# ADC.net
KiCad netlist of a schematic drawn in Altium Designer
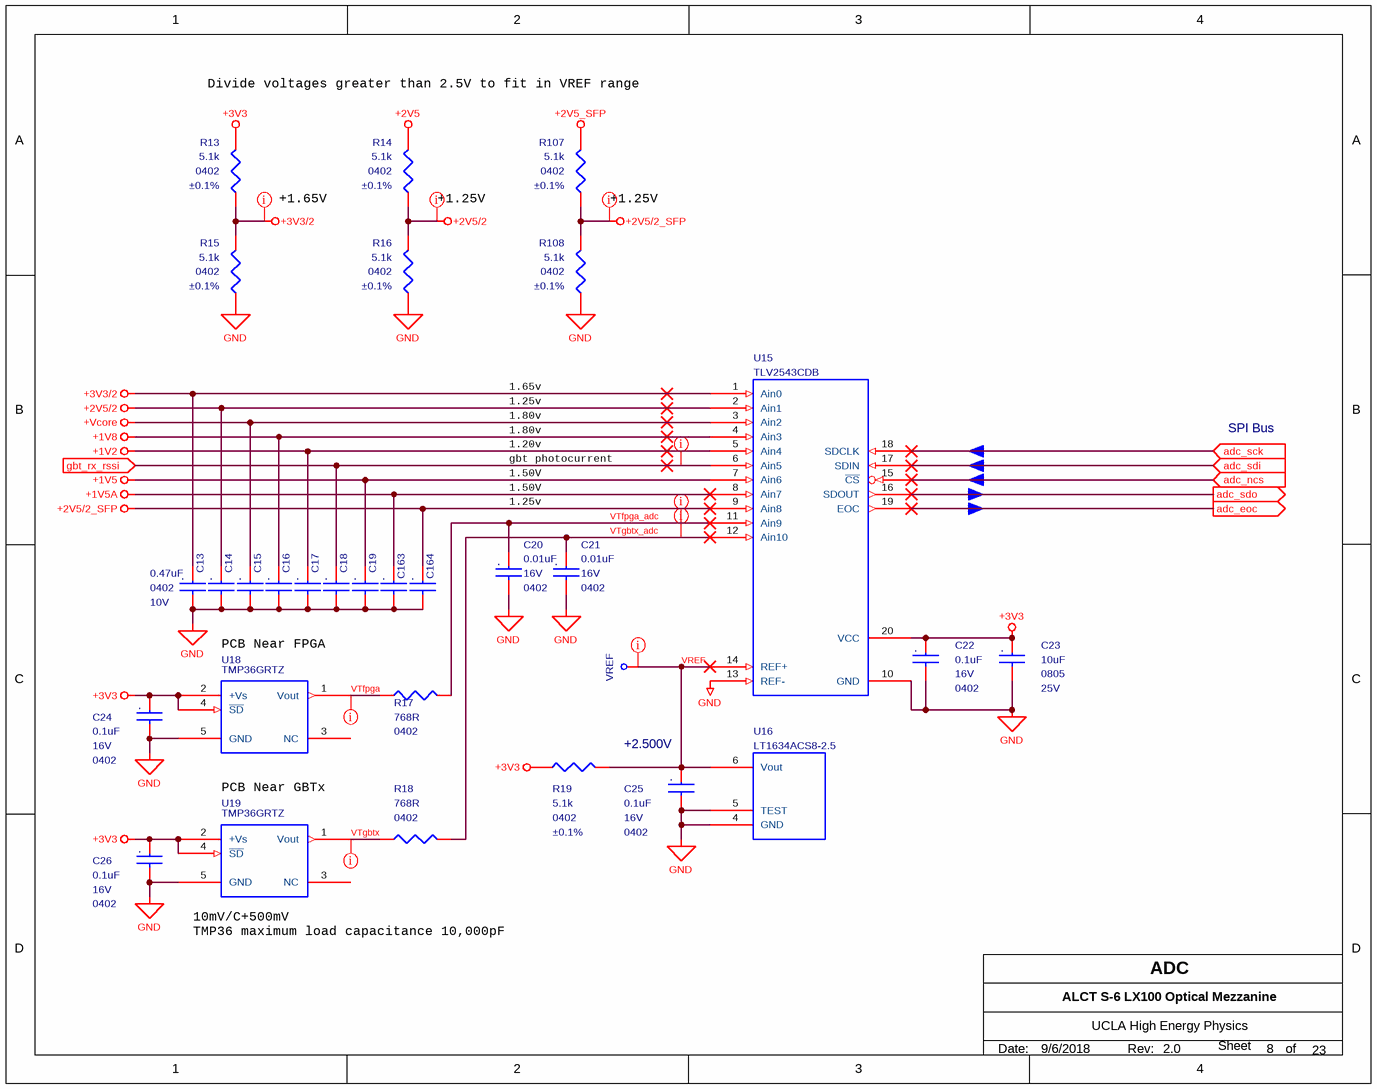
[diagram p0: ADC.SchDoc]

(export (version "E")
  (design (tool "Eeschema 10.0.6"))
  (components
    (comp (ref "C13")
      (value "0.47uF")
      (footprint "MC_S6/SM/C_0402_IPC")
      (description "CAP CER 0.47UF 10V X5R 0402")
      (fields
        (field (name "MANUFACTURER") "Murata Electronics North America")
        (field (name "MANUFACTURER PART NUMBER") "GRM155R61A474KE15D")
        (field (name "PACKAGE") "0402")
        (field (name "VOLTAGE - RATED") "10V")
      )
      (libsource (lib "ALCT_MEZ_SPARTAN6_Library") (part "GRM155R61A474KE15D"))
    )
    (comp (ref "C14")
      (value "0.47uF")
      (footprint "MC_S6/SM/C_0402_IPC")
      (description "CAP CER 0.47UF 10V X5R 0402")
      (fields
        (field (name "MANUFACTURER") "Murata Electronics North America")
        (field (name "MANUFACTURER PART NUMBER") "GRM155R61A474KE15D")
      )
      (libsource (lib "ALCT_MEZ_SPARTAN6_Library") (part "GRM155R61A474KE15D"))
    )
    (comp (ref "C15")
      (value "0.47uF")
      (footprint "MC_S6/SM/C_0402_IPC")
      (description "CAP CER 0.47UF 10V X5R 0402")
      (fields
        (field (name "MANUFACTURER") "Murata Electronics North America")
        (field (name "MANUFACTURER PART NUMBER") "GRM155R61A474KE15D")
      )
      (libsource (lib "ALCT_MEZ_SPARTAN6_Library") (part "GRM155R61A474KE15D"))
    )
    (comp (ref "C16")
      (value "0.47uF")
      (footprint "MC_S6/SM/C_0402_IPC")
      (description "CAP CER 0.47UF 10V X5R 0402")
      (fields
        (field (name "MANUFACTURER") "Murata Electronics North America")
        (field (name "MANUFACTURER PART NUMBER") "GRM155R61A474KE15D")
      )
      (libsource (lib "ALCT_MEZ_SPARTAN6_Library") (part "GRM155R61A474KE15D"))
    )
    (comp (ref "C17")
      (value "0.47uF")
      (footprint "MC_S6/SM/C_0402_IPC")
      (description "CAP CER 0.47UF 10V X5R 0402")
      (fields
        (field (name "MANUFACTURER") "Murata Electronics North America")
        (field (name "MANUFACTURER PART NUMBER") "GRM155R61A474KE15D")
      )
      (libsource (lib "ALCT_MEZ_SPARTAN6_Library") (part "GRM155R61A474KE15D"))
    )
    (comp (ref "C18")
      (value "0.47uF")
      (footprint "MC_S6/SM/C_0402_IPC")
      (description "CAP CER 0.47UF 10V X5R 0402")
      (fields
        (field (name "MANUFACTURER") "Murata Electronics North America")
        (field (name "MANUFACTURER PART NUMBER") "GRM155R61A474KE15D")
      )
      (libsource (lib "ALCT_MEZ_SPARTAN6_Library") (part "GRM155R61A474KE15D"))
    )
    (comp (ref "C19")
      (value "0.47uF")
      (footprint "MC_S6/SM/C_0402_IPC")
      (description "CAP CER 0.47UF 10V X5R 0402")
      (fields
        (field (name "MANUFACTURER") "Murata Electronics North America")
        (field (name "MANUFACTURER PART NUMBER") "GRM155R61A474KE15D")
      )
      (libsource (lib "ALCT_MEZ_SPARTAN6_Library") (part "GRM155R61A474KE15D"))
    )
    (comp (ref "C20")
      (value "0.01uF")
      (footprint "MC_S6/SM/C_0402_IPC")
      (description "CAP CER 10nF 16V X7R 0402")
      (fields
        (field (name "MANUFACTURER") "KEMET")
        (field (name "MANUFACTURER PART NUMBER") "C0402C103K4RACTU")
        (field (name "VOLTAGE - RATED") "16V")
        (field (name "PACKAGE") "0402")
      )
      (libsource (lib "ALCT_MEZ_SPARTAN6_Library") (part "C0402C103K4RACTU"))
    )
    (comp (ref "C21")
      (value "0.01uF")
      (footprint "MC_S6/SM/C_0402_IPC")
      (description "CAP CER 10nF 16V X7R 0402")
      (fields
        (field (name "MANUFACTURER") "KEMET")
        (field (name "MANUFACTURER PART NUMBER") "C0402C103K4RACTU")
        (field (name "VOLTAGE - RATED") "16V")
        (field (name "PACKAGE") "0402")
      )
      (libsource (lib "ALCT_MEZ_SPARTAN6_Library") (part "C0402C103K4RACTU"))
    )
    (comp (ref "C22")
      (value "0.1uF")
      (footprint "MC_S6/SM/C_0402_IPC")
      (description "CAP CER 0.1UF 16V X7R 0402")
      (fields
        (field (name "MANUFACTURER") "KEMET")
        (field (name "MANUFACTURER PART NUMBER") "C0402C104K4RACTU")
        (field (name "PACKAGE") "0402")
        (field (name "VOLTAGE - RATED") "16V")
      )
      (libsource (lib "ALCT_MEZ_SPARTAN6_Library") (part "C0402C104K4RACTU"))
    )
    (comp (ref "C23")
      (value "10uF")
      (footprint "MC_S6/SM/C_0805_IPC")
      (description "CAP CER 10UF 25V X5R 0805")
      (fields
        (field (name "MANUFACTURER") "Murata Electronics North America")
        (field (name "MANUFACTURER PART NUMBER") "GRM21BR61E106KA73L")
        (field (name "VOLTAGE - RATED") "25V")
        (field (name "PACKAGE") "0805")
      )
      (libsource (lib "ALCT_MEZ_SPARTAN6_Library") (part "GRM21BR61E106KA73L"))
    )
    (comp (ref "C24")
      (value "0.1uF")
      (footprint "MC_S6/SM/C_0402_IPC")
      (description "CAP CER 0.1UF 16V X7R 0402")
      (fields
        (field (name "MANUFACTURER") "KEMET")
        (field (name "MANUFACTURER PART NUMBER") "C0402C104K4RACTU")
        (field (name "PACKAGE") "0402")
        (field (name "VOLTAGE - RATED") "16V")
      )
      (libsource (lib "ALCT_MEZ_SPARTAN6_Library") (part "C0402C104K4RACTU"))
    )
    (comp (ref "C25")
      (value "0.1uF")
      (footprint "MC_S6/SM/C_0402_IPC")
      (description "CAP CER 0.1UF 16V X7R 0402")
      (fields
        (field (name "MANUFACTURER") "KEMET")
        (field (name "MANUFACTURER PART NUMBER") "C0402C104K4RACTU")
        (field (name "PACKAGE") "0402")
        (field (name "VOLTAGE - RATED") "16V")
      )
      (libsource (lib "ALCT_MEZ_SPARTAN6_Library") (part "C0402C104K4RACTU"))
    )
    (comp (ref "C26")
      (value "0.1uF")
      (footprint "MC_S6/SM/C_0402_IPC")
      (description "CAP CER 0.1UF 16V X7R 0402")
      (fields
        (field (name "MANUFACTURER") "KEMET")
        (field (name "MANUFACTURER PART NUMBER") "C0402C104K4RACTU")
        (field (name "PACKAGE") "0402")
        (field (name "VOLTAGE - RATED") "16V")
      )
      (libsource (lib "ALCT_MEZ_SPARTAN6_Library") (part "C0402C104K4RACTU"))
    )
    (comp (ref "C163")
      (value "0.47uF")
      (footprint "MC_S6/SM/C_0402_IPC")
      (description "CAP CER 0.47UF 10V X5R 0402")
      (fields
        (field (name "MANUFACTURER") "Murata Electronics North America")
        (field (name "MANUFACTURER PART NUMBER") "GRM155R61A474KE15D")
      )
      (libsource (lib "ALCT_MEZ_SPARTAN6_Library") (part "GRM155R61A474KE15D"))
    )
    (comp (ref "C164")
      (value "0.47uF")
      (footprint "MC_S6/SM/C_0402_IPC")
      (description "CAP CER 0.47UF 10V X5R 0402")
      (fields
        (field (name "MANUFACTURER") "Murata Electronics North America")
        (field (name "MANUFACTURER PART NUMBER") "GRM155R61A474KE15D")
      )
      (libsource (lib "ALCT_MEZ_SPARTAN6_Library") (part "GRM155R61A474KE15D"))
    )
    (comp (ref "R13")
      (value "5.1k")
      (footprint "MC_S6/SM/R_0402_IPC")
      (description "RES SMD 5.1K OHM 0.1% 1/16W 0402")
      (fields
        (field (name "TOLERANCE") "±0.1%")
        (field (name "MANUFACTURER") "Panasonic Electronic Components")
        (field (name "MANUFACTURER PART NUMBER") "ERA-2AEB512X")
        (field (name "SUPPLIER DEVICE PACKAGE") "0402")
      )
      (libsource (lib "ALCT_MEZ_SPARTAN6_Library") (part "ERA-2AEB512X"))
    )
    (comp (ref "R14")
      (value "5.1k")
      (footprint "MC_S6/SM/R_0402_IPC")
      (description "RES SMD 5.1K OHM 0.1% 1/16W 0402")
      (fields
        (field (name "TOLERANCE") "±0.1%")
        (field (name "MANUFACTURER") "Panasonic Electronic Components")
        (field (name "MANUFACTURER PART NUMBER") "ERA-2AEB512X")
        (field (name "SUPPLIER DEVICE PACKAGE") "0402")
      )
      (libsource (lib "ALCT_MEZ_SPARTAN6_Library") (part "ERA-2AEB512X"))
    )
    (comp (ref "R15")
      (value "5.1k")
      (footprint "MC_S6/SM/R_0402_IPC")
      (description "RES SMD 5.1K OHM 0.1% 1/16W 0402")
      (fields
        (field (name "TOLERANCE") "±0.1%")
        (field (name "MANUFACTURER") "Panasonic Electronic Components")
        (field (name "MANUFACTURER PART NUMBER") "ERA-2AEB512X")
        (field (name "SUPPLIER DEVICE PACKAGE") "0402")
      )
      (libsource (lib "ALCT_MEZ_SPARTAN6_Library") (part "ERA-2AEB512X"))
    )
    (comp (ref "R16")
      (value "5.1k")
      (footprint "MC_S6/SM/R_0402_IPC")
      (description "RES SMD 5.1K OHM 0.1% 1/16W 0402")
      (fields
        (field (name "TOLERANCE") "±0.1%")
        (field (name "MANUFACTURER") "Panasonic Electronic Components")
        (field (name "MANUFACTURER PART NUMBER") "ERA-2AEB512X")
        (field (name "SUPPLIER DEVICE PACKAGE") "0402")
      )
      (libsource (lib "ALCT_MEZ_SPARTAN6_Library") (part "ERA-2AEB512X"))
    )
    (comp (ref "R17")
      (value "768R")
      (footprint "MC_S6/SM/R_0402_IPC")
      (description "RES SMD 768 OHM 5.0% 1/10W 0402")
      (fields
        (field (name "TOLERANCE") "±1%")
        (field (name "MANUFACTURER") "Panasonic Electronic Components")
        (field (name "SUPPLIER DEVICE PACKAGE") "0402")
      )
      (libsource (lib "ALCT_MEZ_SPARTAN6_Library") (part "ERJ-2RKF7680X"))
    )
    (comp (ref "R18")
      (value "768R")
      (footprint "MC_S6/SM/R_0402_IPC")
      (description "RES SMD 768 OHM 5.0% 1/10W 0402")
      (fields
        (field (name "TOLERANCE") "±1%")
        (field (name "MANUFACTURER") "Panasonic Electronic Components")
        (field (name "SUPPLIER DEVICE PACKAGE") "0402")
      )
      (libsource (lib "ALCT_MEZ_SPARTAN6_Library") (part "ERJ-2RKF7680X"))
    )
    (comp (ref "R19")
      (value "5.1k")
      (footprint "MC_S6/SM/R_0402_IPC")
      (description "RES SMD 5.1K OHM 0.1% 1/16W 0402")
      (fields
        (field (name "TOLERANCE") "±0.1%")
        (field (name "MANUFACTURER") "Panasonic Electronic Components")
        (field (name "MANUFACTURER PART NUMBER") "ERA-2AEB512X")
        (field (name "SUPPLIER DEVICE PACKAGE") "0402")
      )
      (libsource (lib "ALCT_MEZ_SPARTAN6_Library") (part "ERA-2AEB512X"))
    )
    (comp (ref "R107")
      (value "5.1k")
      (footprint "MC_S6/SM/R_0402_IPC")
      (description "RES SMD 5.1K OHM 0.1% 1/16W 0402")
      (fields
        (field (name "TOLERANCE") "±0.1%")
        (field (name "MANUFACTURER") "Panasonic Electronic Components")
        (field (name "MANUFACTURER PART NUMBER") "ERA-2AEB512X")
        (field (name "SUPPLIER DEVICE PACKAGE") "0402")
      )
      (libsource (lib "ALCT_MEZ_SPARTAN6_Library") (part "ERA-2AEB512X"))
    )
    (comp (ref "R108")
      (value "5.1k")
      (footprint "MC_S6/SM/R_0402_IPC")
      (description "RES SMD 5.1K OHM 0.1% 1/16W 0402")
      (fields
        (field (name "TOLERANCE") "±0.1%")
        (field (name "MANUFACTURER") "Panasonic Electronic Components")
        (field (name "MANUFACTURER PART NUMBER") "ERA-2AEB512X")
        (field (name "SUPPLIER DEVICE PACKAGE") "0402")
      )
      (libsource (lib "ALCT_MEZ_SPARTAN6_Library") (part "ERA-2AEB512X"))
    )
    (comp (ref "U15")
      (value "TLV2543CDB")
      (footprint "MC_S6/SM/ADC_DB20")
      (description "IC SERIAL OUT A/D 11-CH 20-SSOP")
      (fields
        (field (name "MANUFACTURER") "Texas Instruments")
        (field (name "MANUFACTURER PART NUMBER") "TLV2543CDBR")
      )
      (libsource (lib "ALCT_MEZ_SPARTAN6_Library") (part "TLV2543CDB"))
    )
    (comp (ref "U16")
      (value "LT1634ACS8-2.5")
      (footprint "MC_S6/SM/LT1634_SOIC8")
      (description "IC VREF SHUNT 2.5V 8SOIC")
      (fields
        (field (name "MANUFACTURER") "Linear Technology")
        (field (name "MANUFACTURER PART NUMBER") "LT1634ACS8-2.5#PBF")
      )
      (libsource (lib "ALCT_MEZ_SPARTAN6_Library") (part "LT1634_2.5V"))
    )
    (comp (ref "U18")
      (value "TMP36GRTZ")
      (footprint "MC_S6/SM/SOT23_RJ5")
      (description "SENSOR TEMP ANLG VOLT SOT-23-5")
      (fields
        (field (name "MANUFACTURER") "Analog Devices")
        (field (name "MANUFACTURER PART NUMBER") "TMP36GRTZ-REEL7")
      )
      (libsource (lib "ALCT_MEZ_SPARTAN6_Library") (part "TMP36GRTZ"))
    )
    (comp (ref "U19")
      (value "TMP36GRTZ")
      (footprint "MC_S6/SM/SOT23_RJ5")
      (description "SENSOR TEMP ANLG VOLT SOT-23-5")
      (fields
        (field (name "MANUFACTURER") "Analog Devices")
        (field (name "MANUFACTURER PART NUMBER") "TMP36GRTZ-REEL7")
      )
      (libsource (lib "ALCT_MEZ_SPARTAN6_Library") (part "TMP36GRTZ"))
    )
    (comp (ref "VREF")
      (value "Test Point Via")
      (footprint "MC_S6/TH/TPVIA")
      (libsource (lib "ALCT_MEZ_SPARTAN6_Library") (part "TPVIA"))
    )
  )
  (nets
    (net (code "1") (name "+1V2") (class "Default")
      (node (ref "C17") (pin "1") (pinfunction "1_1") (pintype "passive"))
      (node (ref "U15") (pin "5") (pinfunction "Ain4_5") (pintype "input"))
    )
    (net (code "2") (name "+1V5") (class "Default")
      (node (ref "C19") (pin "1") (pinfunction "1_1") (pintype "passive"))
      (node (ref "U15") (pin "7") (pinfunction "Ain6_7") (pintype "input"))
    )
    (net (code "3") (name "+1V5A") (class "Default")
      (node (ref "C163") (pin "1") (pinfunction "1_1") (pintype "passive"))
      (node (ref "U15") (pin "8") (pinfunction "Ain7_8") (pintype "input"))
    )
    (net (code "4") (name "+1V8") (class "Default")
      (node (ref "C16") (pin "1") (pinfunction "1_1") (pintype "passive"))
      (node (ref "U15") (pin "4") (pinfunction "Ain3_4") (pintype "input"))
    )
    (net (code "5") (name "+2V5") (class "Default")
      (node (ref "R14") (pin "1") (pinfunction "1_1") (pintype "passive"))
    )
    (net (code "6") (name "+2V5_SFP") (class "Default")
      (node (ref "R107") (pin "1") (pinfunction "1_1") (pintype "passive"))
    )
    (net (code "7") (name "+2V5{slash}2") (class "Default")
      (node (ref "C14") (pin "1") (pinfunction "1_1") (pintype "passive"))
      (node (ref "R14") (pin "2") (pinfunction "2_2") (pintype "passive"))
      (node (ref "R16") (pin "1") (pinfunction "1_1") (pintype "passive"))
      (node (ref "U15") (pin "2") (pinfunction "Ain1_2") (pintype "input"))
    )
    (net (code "8") (name "+2V5{slash}2_SFP") (class "Default")
      (node (ref "C164") (pin "1") (pinfunction "1_1") (pintype "passive"))
      (node (ref "R107") (pin "2") (pinfunction "2_2") (pintype "passive"))
      (node (ref "R108") (pin "1") (pinfunction "1_1") (pintype "passive"))
      (node (ref "U15") (pin "9") (pinfunction "Ain8_9") (pintype "input"))
    )
    (net (code "9") (name "+3V3") (class "Default")
      (node (ref "C22") (pin "1") (pinfunction "1_1") (pintype "passive"))
      (node (ref "C23") (pin "1") (pinfunction "1_1") (pintype "passive"))
      (node (ref "C24") (pin "1") (pinfunction "1_1") (pintype "passive"))
      (node (ref "C26") (pin "1") (pinfunction "1_1") (pintype "passive"))
      (node (ref "R13") (pin "1") (pinfunction "1_1") (pintype "passive"))
      (node (ref "R19") (pin "1") (pinfunction "1_1") (pintype "passive"))
      (node (ref "U15") (pin "20") (pinfunction "VCC_20") (pintype "power_in"))
      (node (ref "U18") (pin "2") (pinfunction "+Vs_2") (pintype "power_in"))
      (node (ref "U18") (pin "4") (pinfunction "~{SD}_4") (pintype "input"))
      (node (ref "U19") (pin "2") (pinfunction "+Vs_2") (pintype "power_in"))
      (node (ref "U19") (pin "4") (pinfunction "~{SD}_4") (pintype "input"))
    )
    (net (code "10") (name "+3V3{slash}2") (class "Default")
      (node (ref "C13") (pin "1") (pinfunction "1_1") (pintype "passive"))
      (node (ref "R13") (pin "2") (pinfunction "2_2") (pintype "passive"))
      (node (ref "R15") (pin "1") (pinfunction "1_1") (pintype "passive"))
      (node (ref "U15") (pin "1") (pinfunction "Ain0_1") (pintype "input"))
    )
    (net (code "11") (name "+Vcore") (class "Default")
      (node (ref "C15") (pin "1") (pinfunction "1_1") (pintype "passive"))
      (node (ref "U15") (pin "3") (pinfunction "Ain2_3") (pintype "input"))
    )
    (net (code "12") (name "/VREF") (class "Default")
      (node (ref "C25") (pin "1") (pinfunction "1_1") (pintype "passive"))
      (node (ref "R19") (pin "2") (pinfunction "2_2") (pintype "passive"))
      (node (ref "U15") (pin "14") (pinfunction "REF+_14") (pintype "input"))
      (node (ref "U16") (pin "6") (pinfunction "Vout_6") (pintype "passive"))
      (node (ref "VREF") (pin "1") (pinfunction "In_1") (pintype "passive"))
    )
    (net (code "13") (name "/VTfpga") (class "Default")
      (node (ref "R17") (pin "1") (pinfunction "1_1") (pintype "passive"))
      (node (ref "U18") (pin "1") (pinfunction "Vout_1") (pintype "output"))
    )
    (net (code "14") (name "/VTfpga_adc") (class "Default")
      (node (ref "C20") (pin "1") (pinfunction "1_1") (pintype "passive"))
      (node (ref "R17") (pin "2") (pinfunction "2_2") (pintype "passive"))
      (node (ref "U15") (pin "11") (pinfunction "Ain9_11") (pintype "input"))
    )
    (net (code "15") (name "/VTgbtx") (class "Default")
      (node (ref "R18") (pin "1") (pinfunction "1_1") (pintype "passive"))
      (node (ref "U19") (pin "1") (pinfunction "Vout_1") (pintype "output"))
    )
    (net (code "16") (name "/VTgbtx_adc") (class "Default")
      (node (ref "C21") (pin "1") (pinfunction "1_1") (pintype "passive"))
      (node (ref "R18") (pin "2") (pinfunction "2_2") (pintype "passive"))
      (node (ref "U15") (pin "12") (pinfunction "Ain10_12") (pintype "input"))
    )
    (net (code "17") (name "/adc_eoc") (class "Default")
      (node (ref "U15") (pin "19") (pinfunction "EOC_19") (pintype "output+no_connect"))
    )
    (net (code "18") (name "/adc_ncs") (class "Default")
      (node (ref "U15") (pin "15") (pinfunction "~{CS}_15") (pintype "input+no_connect"))
    )
    (net (code "19") (name "/adc_sck") (class "Default")
      (node (ref "U15") (pin "18") (pinfunction "SDCLK_18") (pintype "input+no_connect"))
    )
    (net (code "20") (name "/adc_sdi") (class "Default")
      (node (ref "U15") (pin "17") (pinfunction "SDIN_17") (pintype "input+no_connect"))
    )
    (net (code "21") (name "/adc_sdo") (class "Default")
      (node (ref "U15") (pin "16") (pinfunction "SDOUT_16") (pintype "output+no_connect"))
    )
    (net (code "22") (name "/gbt_rx_rssi") (class "Default")
      (node (ref "C18") (pin "1") (pinfunction "1_1") (pintype "passive"))
      (node (ref "U15") (pin "6") (pinfunction "Ain5_6") (pintype "input"))
    )
    (net (code "23") (name "GND") (class "Default")
      (node (ref "C13") (pin "2") (pinfunction "2_2") (pintype "passive"))
      (node (ref "C14") (pin "2") (pinfunction "2_2") (pintype "passive"))
      (node (ref "C15") (pin "2") (pinfunction "2_2") (pintype "passive"))
      (node (ref "C16") (pin "2") (pinfunction "2_2") (pintype "passive"))
      (node (ref "C163") (pin "2") (pinfunction "2_2") (pintype "passive"))
      (node (ref "C164") (pin "2") (pinfunction "2_2") (pintype "passive"))
      (node (ref "C17") (pin "2") (pinfunction "2_2") (pintype "passive"))
      (node (ref "C18") (pin "2") (pinfunction "2_2") (pintype "passive"))
      (node (ref "C19") (pin "2") (pinfunction "2_2") (pintype "passive"))
      (node (ref "C20") (pin "2") (pinfunction "2_2") (pintype "passive"))
      (node (ref "C21") (pin "2") (pinfunction "2_2") (pintype "passive"))
      (node (ref "C22") (pin "2") (pinfunction "2_2") (pintype "passive"))
      (node (ref "C23") (pin "2") (pinfunction "2_2") (pintype "passive"))
      (node (ref "C24") (pin "2") (pinfunction "2_2") (pintype "passive"))
      (node (ref "C25") (pin "2") (pinfunction "2_2") (pintype "passive"))
      (node (ref "C26") (pin "2") (pinfunction "2_2") (pintype "passive"))
      (node (ref "R108") (pin "2") (pinfunction "2_2") (pintype "passive"))
      (node (ref "R15") (pin "2") (pinfunction "2_2") (pintype "passive"))
      (node (ref "R16") (pin "2") (pinfunction "2_2") (pintype "passive"))
      (node (ref "U15") (pin "10") (pinfunction "GND_10") (pintype "power_in"))
      (node (ref "U15") (pin "13") (pinfunction "REF-_13") (pintype "input"))
      (node (ref "U16") (pin "4") (pinfunction "GND_4") (pintype "power_in"))
      (node (ref "U16") (pin "5") (pinfunction "TEST_5") (pintype "passive"))
      (node (ref "U18") (pin "5") (pinfunction "GND_5") (pintype "power_in"))
      (node (ref "U19") (pin "5") (pinfunction "GND_5") (pintype "power_in"))
    )
    (net (code "24") (name "unconnected-(U18-NC-Pad3)") (class "Default")
      (node (ref "U18") (pin "3") (pinfunction "NC_3") (pintype "passive"))
    )
    (net (code "25") (name "unconnected-(U19-NC-Pad3)") (class "Default")
      (node (ref "U19") (pin "3") (pinfunction "NC_3") (pintype "passive"))
    )
  )
)
